# PWM.net
KiCad netlist of a schematic drawn in EAGLE
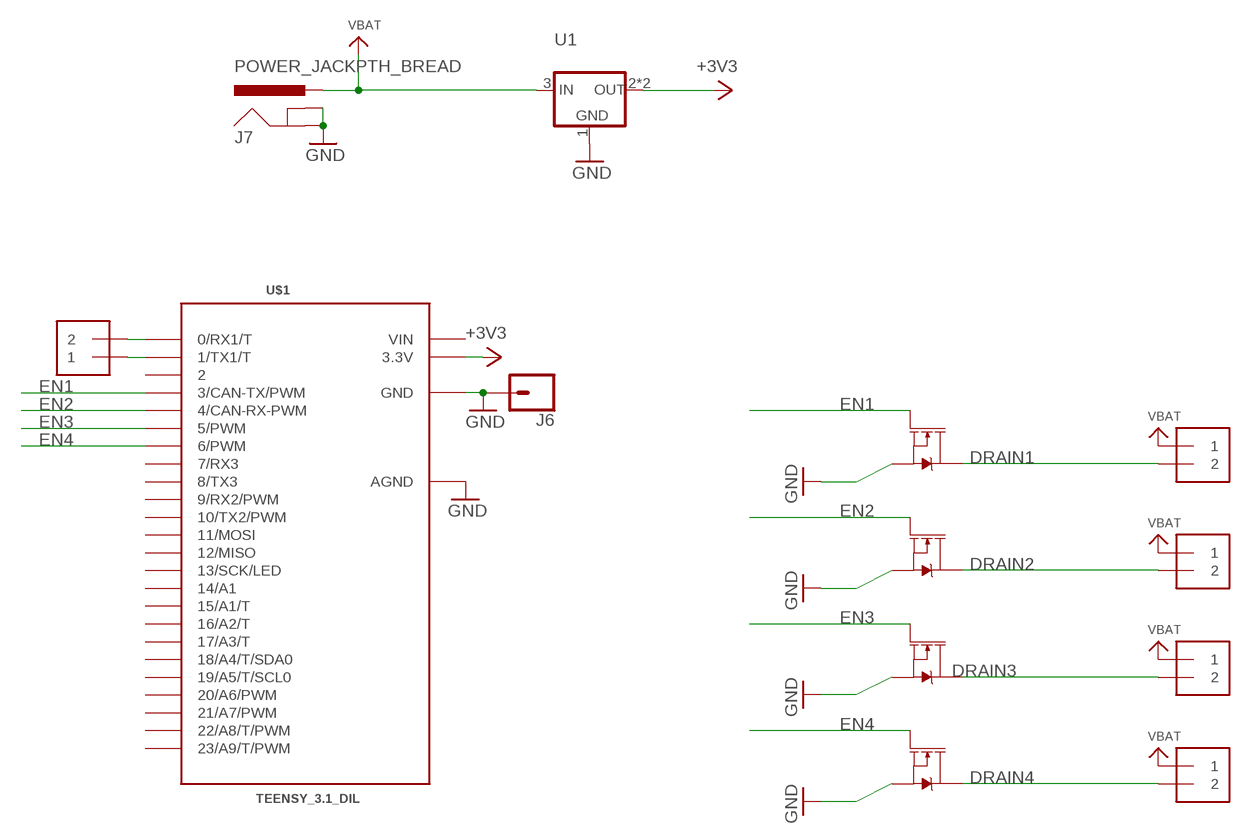
[diagram p0: schematic, sheet 1]

(export (version "E")
  (design (tool "Eeschema 10.0.6"))
  (components
    (comp (ref "J1")
      (value "1X2-3.5MM")
      (footprint "eagle-import:1X2-3.5MM")
      (libsource (lib "eagle-import") (part "1X2-3.5MM"))
    )
    (comp (ref "J2")
      (value "1X2-3.5MM")
      (footprint "eagle-import:1X2-3.5MM")
      (libsource (lib "eagle-import") (part "1X2-3.5MM"))
    )
    (comp (ref "J3")
      (value "1X2-3.5MM")
      (footprint "eagle-import:1X2-3.5MM")
      (libsource (lib "eagle-import") (part "1X2-3.5MM"))
    )
    (comp (ref "J4")
      (value "1X2-3.5MM")
      (footprint "eagle-import:1X2-3.5MM")
      (libsource (lib "eagle-import") (part "1X2-3.5MM"))
    )
    (comp (ref "J5")
      (value "1X2-3.5MM")
      (footprint "eagle-import:1X2-3.5MM")
      (libsource (lib "eagle-import") (part "1X2-3.5MM"))
    )
    (comp (ref "J6")
      (value "CONN_01")
      (footprint "eagle-import:1X01")
      (libsource (lib "eagle-import") (part "CONN_01"))
    )
    (comp (ref "J7")
      (value "POWER_JACKPTH_BREAD")
      (footprint "eagle-import:POWER_JACK_PTH_BREAD")
      (libsource (lib "eagle-import") (part "POWER_JACKPTH_BREAD"))
    )
    (comp (ref "Q1")
      (value "35A/25V/8.5mΩ")
      (footprint "eagle-import:DPAK")
      (libsource (lib "eagle-import") (part "MOSFET-NCH-FDD8780"))
    )
    (comp (ref "Q3")
      (value "35A/25V/8.5mΩ")
      (footprint "eagle-import:DPAK")
      (libsource (lib "eagle-import") (part "MOSFET-NCH-FDD8780"))
    )
    (comp (ref "Q5")
      (value "35A/25V/8.5mΩ")
      (footprint "eagle-import:DPAK")
      (libsource (lib "eagle-import") (part "MOSFET-NCH-FDD8780"))
    )
    (comp (ref "Q6")
      (value "35A/25V/8.5mΩ")
      (footprint "eagle-import:DPAK")
      (libsource (lib "eagle-import") (part "MOSFET-NCH-FDD8780"))
    )
    (comp (ref "U$1")
      (value "TEENSY_3.1_DIL")
      (footprint "eagle-import:TEENSY3-DIL")
      (libsource (lib "eagle-import") (part "TEENSY_3.1_DIL"))
    )
    (comp (ref "U1")
      (value "VREG_SOT223")
      (footprint "eagle-import:SOT223-R")
      (libsource (lib "eagle-import") (part "VREG_SOT223"))
    )
  )
  (nets
    (net (code "1") (name "+3V3") (class "Default")
      (node (ref "U$1") (pin "3.3V") (pinfunction "3.3V_3.3V") (pintype "power_in"))
      (node (ref "U1") (pin "2") (pinfunction "OUT_2") (pintype "power_in"))
      (node (ref "U1") (pin "4") (pinfunction "OUT_4") (pintype "power_in"))
    )
    (net (code "2") (name "/DRAIN1") (class "Default")
      (node (ref "J2") (pin "2") (pinfunction "2_2") (pintype "passive"))
      (node (ref "Q1") (pin "4") (pinfunction "D_4") (pintype "bidirectional"))
    )
    (net (code "3") (name "/DRAIN2") (class "Default")
      (node (ref "J3") (pin "2") (pinfunction "2_2") (pintype "passive"))
      (node (ref "Q3") (pin "4") (pinfunction "D_4") (pintype "bidirectional"))
    )
    (net (code "4") (name "/DRAIN3") (class "Default")
      (node (ref "J4") (pin "2") (pinfunction "2_2") (pintype "passive"))
      (node (ref "Q5") (pin "4") (pinfunction "D_4") (pintype "bidirectional"))
    )
    (net (code "5") (name "/DRAIN4") (class "Default")
      (node (ref "J5") (pin "2") (pinfunction "2_2") (pintype "passive"))
      (node (ref "Q6") (pin "4") (pinfunction "D_4") (pintype "bidirectional"))
    )
    (net (code "6") (name "/EN1") (class "Default")
      (node (ref "Q1") (pin "1") (pinfunction "G_1") (pintype "bidirectional"))
      (node (ref "U$1") (pin "3") (pinfunction "3/CAN-TX/PWM_3") (pintype "bidirectional"))
    )
    (net (code "7") (name "/EN2") (class "Default")
      (node (ref "Q3") (pin "1") (pinfunction "G_1") (pintype "bidirectional"))
      (node (ref "U$1") (pin "4") (pinfunction "4/CAN-RX-PWM_4") (pintype "bidirectional"))
    )
    (net (code "8") (name "/EN3") (class "Default")
      (node (ref "Q5") (pin "1") (pinfunction "G_1") (pintype "bidirectional"))
      (node (ref "U$1") (pin "5") (pinfunction "5/PWM_5") (pintype "bidirectional"))
    )
    (net (code "9") (name "/EN4") (class "Default")
      (node (ref "Q6") (pin "1") (pinfunction "G_1") (pintype "bidirectional"))
      (node (ref "U$1") (pin "6") (pinfunction "6/PWM_6") (pintype "bidirectional"))
    )
    (net (code "10") (name "/VIN") (class "Default")
      (node (ref "U$1") (pin "VIN") (pinfunction "VIN_VIN") (pintype "power_in"))
    )
    (net (code "11") (name "GND") (class "Default")
      (node (ref "J6") (pin "1") (pinfunction "1_1") (pintype "passive"))
      (node (ref "J7") (pin "GND") (pinfunction "GND_GND") (pintype "bidirectional"))
      (node (ref "J7") (pin "GNDBREAK") (pinfunction "GNDBREAK_GNDBREAK") (pintype "bidirectional"))
      (node (ref "Q1") (pin "3") (pinfunction "S_3") (pintype "bidirectional"))
      (node (ref "Q3") (pin "3") (pinfunction "S_3") (pintype "bidirectional"))
      (node (ref "Q5") (pin "3") (pinfunction "S_3") (pintype "bidirectional"))
      (node (ref "Q6") (pin "3") (pinfunction "S_3") (pintype "bidirectional"))
      (node (ref "U$1") (pin "AGND") (pinfunction "AGND_AGND") (pintype "power_in"))
      (node (ref "U$1") (pin "GND") (pinfunction "GND_GND") (pintype "power_in"))
      (node (ref "U1") (pin "1") (pinfunction "GND_1") (pintype "power_in"))
    )
    (net (code "12") (name "Net-(U$1-0{slash}RX1{slash}T)") (class "Default")
      (node (ref "J1") (pin "2") (pinfunction "2_2") (pintype "passive"))
      (node (ref "U$1") (pin "0") (pinfunction "0/RX1/T_0") (pintype "bidirectional"))
    )
    (net (code "13") (name "Net-(U$1-1{slash}TX1{slash}T)") (class "Default")
      (node (ref "J1") (pin "1") (pinfunction "1_1") (pintype "passive"))
      (node (ref "U$1") (pin "1") (pinfunction "1/TX1/T_1") (pintype "bidirectional"))
    )
    (net (code "14") (name "VBAT") (class "Default")
      (node (ref "J2") (pin "1") (pinfunction "1_1") (pintype "passive"))
      (node (ref "J3") (pin "1") (pinfunction "1_1") (pintype "passive"))
      (node (ref "J4") (pin "1") (pinfunction "1_1") (pintype "passive"))
      (node (ref "J5") (pin "1") (pinfunction "1_1") (pintype "passive"))
      (node (ref "J7") (pin "PWR") (pinfunction "PWR_PWR") (pintype "bidirectional"))
      (node (ref "U1") (pin "3") (pinfunction "IN_3") (pintype "power_in"))
    )
    (net (code "15") (name "unconnected-(U$1-7{slash}RX3-Pad7)") (class "Default")
      (node (ref "U$1") (pin "7") (pinfunction "7/RX3_7") (pintype "bidirectional"))
    )
    (net (code "16") (name "unconnected-(U$1-8{slash}TX3-Pad8)") (class "Default")
      (node (ref "U$1") (pin "8") (pinfunction "8/TX3_8") (pintype "bidirectional"))
    )
    (net (code "17") (name "unconnected-(U$1-9{slash}RX2{slash}PWM-Pad9)") (class "Default")
      (node (ref "U$1") (pin "9") (pinfunction "9/RX2/PWM_9") (pintype "bidirectional"))
    )
    (net (code "18") (name "unconnected-(U$1-10{slash}TX2{slash}PWM-Pad10)") (class "Default")
      (node (ref "U$1") (pin "10") (pinfunction "10/TX2/PWM_10") (pintype "bidirectional"))
    )
    (net (code "19") (name "unconnected-(U$1-11{slash}MOSI-Pad11)") (class "Default")
      (node (ref "U$1") (pin "11") (pinfunction "11/MOSI_11") (pintype "bidirectional"))
    )
    (net (code "20") (name "unconnected-(U$1-12{slash}MISO-Pad12)") (class "Default")
      (node (ref "U$1") (pin "12") (pinfunction "12/MISO_12") (pintype "bidirectional"))
    )
    (net (code "21") (name "unconnected-(U$1-13{slash}SCK{slash}LED-Pad13)") (class "Default")
      (node (ref "U$1") (pin "13") (pinfunction "13/SCK/LED_13") (pintype "bidirectional"))
    )
    (net (code "22") (name "unconnected-(U$1-14{slash}A1-Pad14{slash}A0)") (class "Default")
      (node (ref "U$1") (pin "14/A0") (pinfunction "14/A1_14/A0") (pintype "bidirectional"))
    )
    (net (code "23") (name "unconnected-(U$1-15{slash}A1{slash}T-Pad15{slash}A1)") (class "Default")
      (node (ref "U$1") (pin "15/A1") (pinfunction "15/A1/T_15/A1") (pintype "bidirectional"))
    )
    (net (code "24") (name "unconnected-(U$1-16{slash}A2{slash}T-Pad16{slash}A2)") (class "Default")
      (node (ref "U$1") (pin "16/A2") (pinfunction "16/A2/T_16/A2") (pintype "bidirectional"))
    )
    (net (code "25") (name "unconnected-(U$1-17{slash}A3{slash}T-Pad17{slash}A3)") (class "Default")
      (node (ref "U$1") (pin "17/A3") (pinfunction "17/A3/T_17/A3") (pintype "bidirectional"))
    )
    (net (code "26") (name "unconnected-(U$1-18{slash}A4{slash}T{slash}SDA0-Pad18{slash}A4)") (class "Default")
      (node (ref "U$1") (pin "18/A4") (pinfunction "18/A4/T/SDA0_18/A4") (pintype "bidirectional"))
    )
    (net (code "27") (name "unconnected-(U$1-19{slash}A5{slash}T{slash}SCL0-Pad19{slash}A5)") (class "Default")
      (node (ref "U$1") (pin "19/A5") (pinfunction "19/A5/T/SCL0_19/A5") (pintype "bidirectional"))
    )
    (net (code "28") (name "unconnected-(U$1-20{slash}A6{slash}PWM-Pad20{slash}A6)") (class "Default")
      (node (ref "U$1") (pin "20/A6") (pinfunction "20/A6/PWM_20/A6") (pintype "bidirectional"))
    )
    (net (code "29") (name "unconnected-(U$1-21{slash}A7{slash}PWM-Pad21{slash}A7)") (class "Default")
      (node (ref "U$1") (pin "21/A7") (pinfunction "21/A7/PWM_21/A7") (pintype "bidirectional"))
    )
    (net (code "30") (name "unconnected-(U$1-22{slash}A8{slash}T{slash}PWM-Pad22{slash}A8)") (class "Default")
      (node (ref "U$1") (pin "22/A8") (pinfunction "22/A8/T/PWM_22/A8") (pintype "bidirectional"))
    )
    (net (code "31") (name "unconnected-(U$1-23{slash}A9{slash}T{slash}PWM-Pad23{slash}A9)") (class "Default")
      (node (ref "U$1") (pin "23/A9") (pinfunction "23/A9/T/PWM_23/A9") (pintype "bidirectional"))
    )
    (net (code "32") (name "unconnected-(U$1-Pad2)") (class "Default")
      (node (ref "U$1") (pin "2") (pinfunction "2_2") (pintype "bidirectional"))
    )
  )
)
